# potenciostat.net
KiCad netlist of a schematic drawn in EAGLE
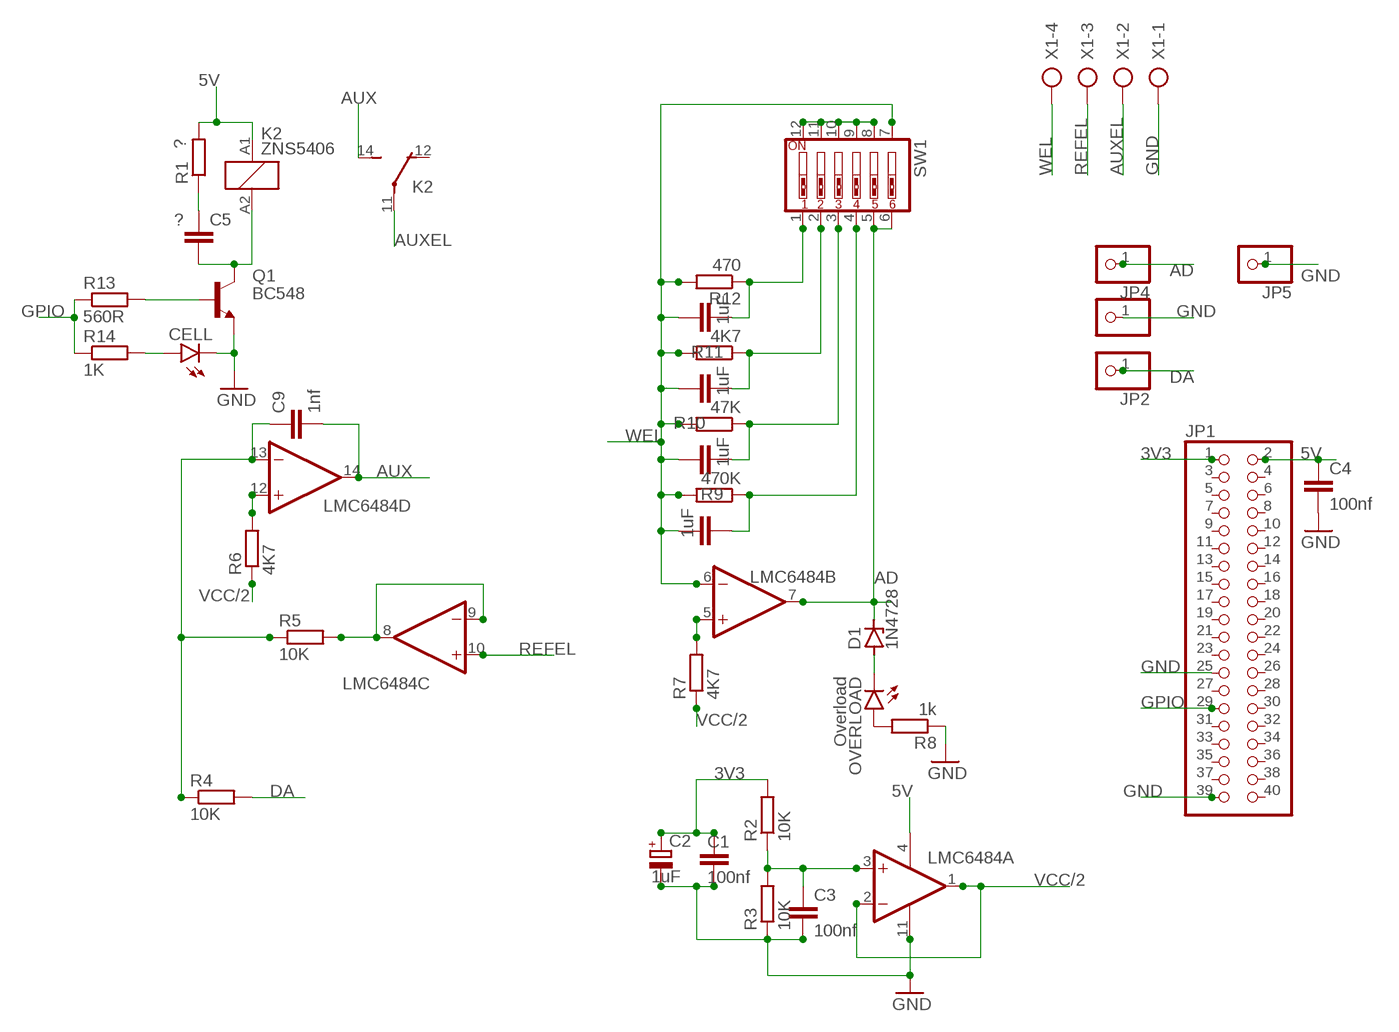
[diagram p0: schematic, sheet 1]

(export (version "E")
  (design (tool "Eeschema 10.0.6"))
  (components
    (comp (ref "C1")
      (value "100nf")
      (footprint "eagle-import:C050-035X075")
      (libsource (lib "eagle-import") (part "C-EU050-035X075"))
    )
    (comp (ref "C2")
      (value "1uF")
      (footprint "eagle-import:E2,5-5")
      (libsource (lib "eagle-import") (part "CPOL-EUE2.5-5"))
    )
    (comp (ref "C3")
      (value "100nf")
      (footprint "eagle-import:C050-035X075")
      (libsource (lib "eagle-import") (part "C-EU050-035X075"))
    )
    (comp (ref "C4")
      (value "100nf")
      (footprint "eagle-import:C050-035X075")
      (libsource (lib "eagle-import") (part "C-EU050-035X075"))
    )
    (comp (ref "C5")
      (value "?")
      (footprint "eagle-import:C050-035X075")
      (libsource (lib "eagle-import") (part "C-EU050-035X075"))
    )
    (comp (ref "C6")
      (value "1uF")
      (footprint "eagle-import:C050-035X075")
      (libsource (lib "eagle-import") (part "C-EU050-035X075"))
    )
    (comp (ref "C7")
      (value "1uF")
      (footprint "eagle-import:C050-035X075")
      (libsource (lib "eagle-import") (part "C-EU050-035X075"))
    )
    (comp (ref "C8")
      (value "1uF")
      (footprint "eagle-import:C050-035X075")
      (libsource (lib "eagle-import") (part "C-EU050-035X075"))
    )
    (comp (ref "C9")
      (value "1nf")
      (footprint "eagle-import:C050-035X075")
      (libsource (lib "eagle-import") (part "C-EU050-035X075"))
    )
    (comp (ref "C10")
      (value "1uF")
      (footprint "eagle-import:C050-035X075")
      (libsource (lib "eagle-import") (part "C-EU050-035X075"))
    )
    (comp (ref "CELL")
      (value "TLLG4400")
      (footprint "eagle-import:LED3MM")
      (fields (field (name "MF") "VISHAY SEMICONDUCTOR"))
      (libsource (lib "eagle-import") (part "TLLG4400"))
    )
    (comp (ref "D1")
      (value "1N4728")
      (footprint "eagle-import:DO41Z10")
      (libsource (lib "eagle-import") (part "1N4728"))
    )
    (comp (ref "JP1")
      (value "PINHD-2X20/90")
      (footprint "eagle-import:2X20_90")
      (libsource (lib "eagle-import") (part "PINHD-2X20/90"))
    )
    (comp (ref "JP2")
      (value "PINHD-1X1")
      (footprint "eagle-import:1X01")
      (libsource (lib "eagle-import") (part "PINHD-1X1"))
    )
    (comp (ref "JP3")
      (value "PINHD-1X1")
      (footprint "eagle-import:1X01")
      (libsource (lib "eagle-import") (part "PINHD-1X1"))
    )
    (comp (ref "JP4")
      (value "PINHD-1X1")
      (footprint "eagle-import:1X01")
      (libsource (lib "eagle-import") (part "PINHD-1X1"))
    )
    (comp (ref "JP5")
      (value "PINHD-1X1")
      (footprint "eagle-import:1X01")
      (libsource (lib "eagle-import") (part "PINHD-1X1"))
    )
    (comp (ref "K2")
      (value "ZNS5406")
      (footprint "eagle-import:ZN5")
      (libsource (lib "eagle-import") (part "ZNS5406"))
    )
    (comp (ref "LMC6484")
      (value "TL074P")
      (footprint "eagle-import:DIL14")
      (libsource (lib "eagle-import") (part "TL074P"))
    )
    (comp (ref "OVERLOAD")
      (value "Overload")
      (footprint "eagle-import:LED3MM")
      (fields (field (name "MF") "VISHAY SEMICONDUCTOR"))
      (libsource (lib "eagle-import") (part "TLLG4400"))
    )
    (comp (ref "Q1")
      (value "BC548")
      (footprint "eagle-import:TO92-EBC")
      (libsource (lib "eagle-import") (part "BC548"))
    )
    (comp (ref "R1")
      (value "?")
      (footprint "eagle-import:0207_7")
      (libsource (lib "eagle-import") (part "R-EU_0207/7"))
    )
    (comp (ref "R2")
      (value "10K")
      (footprint "eagle-import:0207_7")
      (libsource (lib "eagle-import") (part "R-EU_0207/7"))
    )
    (comp (ref "R3")
      (value "10K")
      (footprint "eagle-import:0207_7")
      (libsource (lib "eagle-import") (part "R-EU_0207/7"))
    )
    (comp (ref "R4")
      (value "10K")
      (footprint "eagle-import:0207_7")
      (libsource (lib "eagle-import") (part "R-EU_0207/7"))
    )
    (comp (ref "R5")
      (value "10K")
      (footprint "eagle-import:0207_7")
      (libsource (lib "eagle-import") (part "R-EU_0207/7"))
    )
    (comp (ref "R6")
      (value "4K7")
      (footprint "eagle-import:0207_7")
      (libsource (lib "eagle-import") (part "R-EU_0207/7"))
    )
    (comp (ref "R7")
      (value "4K7")
      (footprint "eagle-import:0207_7")
      (libsource (lib "eagle-import") (part "R-EU_0207/7"))
    )
    (comp (ref "R8")
      (value "1k")
      (footprint "eagle-import:0207_7")
      (libsource (lib "eagle-import") (part "R-EU_0207/7"))
    )
    (comp (ref "R9")
      (value "470K")
      (footprint "eagle-import:0207_7")
      (libsource (lib "eagle-import") (part "R-EU_0207/7"))
    )
    (comp (ref "R10")
      (value "47K")
      (footprint "eagle-import:0207_7")
      (libsource (lib "eagle-import") (part "R-EU_0207/7"))
    )
    (comp (ref "R11")
      (value "4K7")
      (footprint "eagle-import:0207_7")
      (libsource (lib "eagle-import") (part "R-EU_0207/7"))
    )
    (comp (ref "R12")
      (value "470")
      (footprint "eagle-import:0207_7")
      (libsource (lib "eagle-import") (part "R-EU_0207/7"))
    )
    (comp (ref "R13")
      (value "560R")
      (footprint "eagle-import:0207_7")
      (libsource (lib "eagle-import") (part "R-EU_0207/7"))
    )
    (comp (ref "R14")
      (value "1K")
      (footprint "eagle-import:0207_7")
      (libsource (lib "eagle-import") (part "R-EU_0207/7"))
    )
    (comp (ref "SW1")
      (value "SW_DIP-6")
      (footprint "eagle-import:EDG-06")
      (libsource (lib "eagle-import") (part "SW_DIP-6"))
    )
    (comp (ref "X1")
      (value "AK500/4")
      (footprint "eagle-import:AK500_4")
      (libsource (lib "eagle-import") (part "AK500/4"))
    )
  )
  (nets
    (net (code "1") (name "/3V3") (class "Default")
      (node (ref "C1") (pin "1") (pinfunction "1_1") (pintype "passive"))
      (node (ref "C2") (pin "+") (pinfunction "+_+") (pintype "passive"))
      (node (ref "JP1") (pin "1") (pinfunction "1_1") (pintype "passive"))
      (node (ref "R2") (pin "2") (pinfunction "2_2") (pintype "passive"))
    )
    (net (code "2") (name "/5V") (class "Default")
      (node (ref "C4") (pin "1") (pinfunction "1_1") (pintype "passive"))
      (node (ref "JP1") (pin "2") (pinfunction "2_2") (pintype "passive"))
      (node (ref "K2") (pin "A1") (pinfunction "1_A1") (pintype "passive"))
      (node (ref "LMC6484") (pin "4") (pinfunction "V+_4") (pintype "power_in"))
      (node (ref "R1") (pin "2") (pinfunction "2_2") (pintype "passive"))
    )
    (net (code "3") (name "/AD") (class "Default")
      (node (ref "D1") (pin "C") (pinfunction "C_C") (pintype "passive"))
      (node (ref "JP4") (pin "1") (pinfunction "1_1") (pintype "passive"))
      (node (ref "LMC6484") (pin "7") (pinfunction "OUT_7") (pintype "output"))
      (node (ref "SW1") (pin "5") (pinfunction "5_5") (pintype "passive"))
      (node (ref "SW1") (pin "6") (pinfunction "6_6") (pintype "passive"))
    )
    (net (code "4") (name "/AUX") (class "Default")
      (node (ref "C9") (pin "2") (pinfunction "2_2") (pintype "passive"))
      (node (ref "K2") (pin "14") (pinfunction "S_14") (pintype "passive"))
      (node (ref "LMC6484") (pin "14") (pinfunction "OUT_14") (pintype "output"))
    )
    (net (code "5") (name "/AUXEL") (class "Default")
      (node (ref "K2") (pin "11") (pinfunction "P_11") (pintype "passive"))
      (node (ref "X1") (pin "2") (pinfunction "KL_2") (pintype "passive"))
    )
    (net (code "6") (name "/DA") (class "Default")
      (node (ref "JP2") (pin "1") (pinfunction "1_1") (pintype "passive"))
      (node (ref "R4") (pin "2") (pinfunction "2_2") (pintype "passive"))
    )
    (net (code "7") (name "/GPIO") (class "Default")
      (node (ref "JP1") (pin "29") (pinfunction "29_29") (pintype "passive"))
      (node (ref "R13") (pin "1") (pinfunction "1_1") (pintype "passive"))
      (node (ref "R14") (pin "1") (pinfunction "1_1") (pintype "passive"))
    )
    (net (code "8") (name "/REFEL") (class "Default")
      (node (ref "LMC6484") (pin "10") (pinfunction "+IN_10") (pintype "input"))
      (node (ref "X1") (pin "3") (pinfunction "KL_3") (pintype "passive"))
    )
    (net (code "9") (name "/VCC{slash}2") (class "Default")
      (node (ref "LMC6484") (pin "1") (pinfunction "OUT_1") (pintype "output"))
      (node (ref "LMC6484") (pin "2") (pinfunction "-IN_2") (pintype "input"))
      (node (ref "R6") (pin "1") (pinfunction "1_1") (pintype "passive"))
      (node (ref "R7") (pin "1") (pinfunction "1_1") (pintype "passive"))
    )
    (net (code "10") (name "/WEL") (class "Default")
      (node (ref "C10") (pin "1") (pinfunction "1_1") (pintype "passive"))
      (node (ref "C6") (pin "1") (pinfunction "1_1") (pintype "passive"))
      (node (ref "C7") (pin "1") (pinfunction "1_1") (pintype "passive"))
      (node (ref "C8") (pin "1") (pinfunction "1_1") (pintype "passive"))
      (node (ref "LMC6484") (pin "6") (pinfunction "-IN_6") (pintype "input"))
      (node (ref "R10") (pin "2") (pinfunction "2_2") (pintype "passive"))
      (node (ref "R11") (pin "2") (pinfunction "2_2") (pintype "passive"))
      (node (ref "R12") (pin "2") (pinfunction "2_2") (pintype "passive"))
      (node (ref "R9") (pin "2") (pinfunction "2_2") (pintype "passive"))
      (node (ref "SW1") (pin "7") (pinfunction "7_7") (pintype "passive"))
      (node (ref "X1") (pin "4") (pinfunction "KL_4") (pintype "passive"))
    )
    (net (code "11") (name "GND") (class "Default")
      (node (ref "C1") (pin "2") (pinfunction "2_2") (pintype "passive"))
      (node (ref "C2") (pin "-") (pinfunction "-_-") (pintype "passive"))
      (node (ref "C3") (pin "2") (pinfunction "2_2") (pintype "passive"))
      (node (ref "C4") (pin "2") (pinfunction "2_2") (pintype "passive"))
      (node (ref "CELL") (pin "K") (pinfunction "C_K") (pintype "passive"))
      (node (ref "JP1") (pin "25") (pinfunction "25_25") (pintype "passive"))
      (node (ref "JP1") (pin "39") (pinfunction "39_39") (pintype "passive"))
      (node (ref "JP3") (pin "1") (pinfunction "1_1") (pintype "passive"))
      (node (ref "JP5") (pin "1") (pinfunction "1_1") (pintype "passive"))
      (node (ref "LMC6484") (pin "11") (pinfunction "V-_11") (pintype "power_in"))
      (node (ref "Q1") (pin "E") (pinfunction "E_E") (pintype "passive"))
      (node (ref "R3") (pin "1") (pinfunction "1_1") (pintype "passive"))
      (node (ref "R8") (pin "1") (pinfunction "1_1") (pintype "passive"))
      (node (ref "X1") (pin "1") (pinfunction "KL_1") (pintype "passive"))
    )
    (net (code "12") (name "Net-(C5-Pad1)") (class "Default")
      (node (ref "C5") (pin "1") (pinfunction "1_1") (pintype "passive"))
      (node (ref "R1") (pin "1") (pinfunction "1_1") (pintype "passive"))
    )
    (net (code "13") (name "Net-(C6-Pad2)") (class "Default")
      (node (ref "C6") (pin "2") (pinfunction "2_2") (pintype "passive"))
      (node (ref "R9") (pin "1") (pinfunction "1_1") (pintype "passive"))
      (node (ref "SW1") (pin "4") (pinfunction "4_4") (pintype "passive"))
    )
    (net (code "14") (name "Net-(C7-Pad2)") (class "Default")
      (node (ref "C7") (pin "2") (pinfunction "2_2") (pintype "passive"))
      (node (ref "R12") (pin "1") (pinfunction "1_1") (pintype "passive"))
      (node (ref "SW1") (pin "1") (pinfunction "1_1") (pintype "passive"))
    )
    (net (code "15") (name "Net-(C8-Pad2)") (class "Default")
      (node (ref "C8") (pin "2") (pinfunction "2_2") (pintype "passive"))
      (node (ref "R11") (pin "1") (pinfunction "1_1") (pintype "passive"))
      (node (ref "SW1") (pin "2") (pinfunction "2_2") (pintype "passive"))
    )
    (net (code "16") (name "Net-(C10-Pad2)") (class "Default")
      (node (ref "C10") (pin "2") (pinfunction "2_2") (pintype "passive"))
      (node (ref "R10") (pin "1") (pinfunction "1_1") (pintype "passive"))
      (node (ref "SW1") (pin "3") (pinfunction "3_3") (pintype "passive"))
    )
    (net (code "17") (name "Net-(CELL-PadA)") (class "Default")
      (node (ref "CELL") (pin "A") (pinfunction "A_A") (pintype "passive"))
      (node (ref "R14") (pin "2") (pinfunction "2_2") (pintype "passive"))
    )
    (net (code "18") (name "Net-(K2A-2)") (class "Default")
      (node (ref "C5") (pin "2") (pinfunction "2_2") (pintype "passive"))
      (node (ref "K2") (pin "A2") (pinfunction "2_A2") (pintype "passive"))
      (node (ref "Q1") (pin "C") (pinfunction "C_C") (pintype "passive"))
    )
    (net (code "19") (name "Net-(LMC6484A-+IN)") (class "Default")
      (node (ref "C3") (pin "1") (pinfunction "1_1") (pintype "passive"))
      (node (ref "LMC6484") (pin "3") (pinfunction "+IN_3") (pintype "input"))
      (node (ref "R2") (pin "1") (pinfunction "1_1") (pintype "passive"))
      (node (ref "R3") (pin "2") (pinfunction "2_2") (pintype "passive"))
    )
    (net (code "20") (name "Net-(LMC6484B-+IN)") (class "Default")
      (node (ref "LMC6484") (pin "5") (pinfunction "+IN_5") (pintype "input"))
      (node (ref "R7") (pin "2") (pinfunction "2_2") (pintype "passive"))
    )
    (net (code "21") (name "Net-(LMC6484C--IN)") (class "Default")
      (node (ref "LMC6484") (pin "8") (pinfunction "OUT_8") (pintype "output"))
      (node (ref "LMC6484") (pin "9") (pinfunction "-IN_9") (pintype "input"))
      (node (ref "R5") (pin "2") (pinfunction "2_2") (pintype "passive"))
    )
    (net (code "22") (name "Net-(LMC6484D-+IN)") (class "Default")
      (node (ref "LMC6484") (pin "12") (pinfunction "+IN_12") (pintype "input"))
      (node (ref "R6") (pin "2") (pinfunction "2_2") (pintype "passive"))
    )
    (net (code "23") (name "Net-(LMC6484D--IN)") (class "Default")
      (node (ref "C9") (pin "1") (pinfunction "1_1") (pintype "passive"))
      (node (ref "LMC6484") (pin "13") (pinfunction "-IN_13") (pintype "input"))
      (node (ref "R4") (pin "1") (pinfunction "1_1") (pintype "passive"))
      (node (ref "R5") (pin "1") (pinfunction "1_1") (pintype "passive"))
    )
    (net (code "24") (name "Net-(OVERLOAD-C)") (class "Default")
      (node (ref "D1") (pin "A") (pinfunction "A_A") (pintype "passive"))
      (node (ref "OVERLOAD") (pin "K") (pinfunction "C_K") (pintype "passive"))
    )
    (net (code "25") (name "Net-(OVERLOAD-PadA)") (class "Default")
      (node (ref "OVERLOAD") (pin "A") (pinfunction "A_A") (pintype "passive"))
      (node (ref "R8") (pin "2") (pinfunction "2_2") (pintype "passive"))
    )
    (net (code "26") (name "Net-(Q1-PadB)") (class "Default")
      (node (ref "Q1") (pin "B") (pinfunction "B_B") (pintype "passive"))
      (node (ref "R13") (pin "2") (pinfunction "2_2") (pintype "passive"))
    )
    (net (code "27") (name "Net-(SW1-Pad10)") (class "Default")
      (node (ref "SW1") (pin "10") (pinfunction "10_10") (pintype "passive"))
      (node (ref "SW1") (pin "11") (pinfunction "11_11") (pintype "passive"))
      (node (ref "SW1") (pin "12") (pinfunction "12_12") (pintype "passive"))
      (node (ref "SW1") (pin "8") (pinfunction "8_8") (pintype "passive"))
      (node (ref "SW1") (pin "9") (pinfunction "9_9") (pintype "passive"))
    )
    (net (code "28") (name "unconnected-(JP1-Pad3)") (class "Default")
      (node (ref "JP1") (pin "3") (pinfunction "3_3") (pintype "passive"))
    )
    (net (code "29") (name "unconnected-(JP1-Pad4)") (class "Default")
      (node (ref "JP1") (pin "4") (pinfunction "4_4") (pintype "passive"))
    )
    (net (code "30") (name "unconnected-(JP1-Pad5)") (class "Default")
      (node (ref "JP1") (pin "5") (pinfunction "5_5") (pintype "passive"))
    )
    (net (code "31") (name "unconnected-(JP1-Pad6)") (class "Default")
      (node (ref "JP1") (pin "6") (pinfunction "6_6") (pintype "passive"))
    )
    (net (code "32") (name "unconnected-(JP1-Pad7)") (class "Default")
      (node (ref "JP1") (pin "7") (pinfunction "7_7") (pintype "passive"))
    )
    (net (code "33") (name "unconnected-(JP1-Pad8)") (class "Default")
      (node (ref "JP1") (pin "8") (pinfunction "8_8") (pintype "passive"))
    )
    (net (code "34") (name "unconnected-(JP1-Pad9)") (class "Default")
      (node (ref "JP1") (pin "9") (pinfunction "9_9") (pintype "passive"))
    )
    (net (code "35") (name "unconnected-(JP1-Pad10)") (class "Default")
      (node (ref "JP1") (pin "10") (pinfunction "10_10") (pintype "passive"))
    )
    (net (code "36") (name "unconnected-(JP1-Pad11)") (class "Default")
      (node (ref "JP1") (pin "11") (pinfunction "11_11") (pintype "passive"))
    )
    (net (code "37") (name "unconnected-(JP1-Pad12)") (class "Default")
      (node (ref "JP1") (pin "12") (pinfunction "12_12") (pintype "passive"))
    )
    (net (code "38") (name "unconnected-(JP1-Pad13)") (class "Default")
      (node (ref "JP1") (pin "13") (pinfunction "13_13") (pintype "passive"))
    )
    (net (code "39") (name "unconnected-(JP1-Pad14)") (class "Default")
      (node (ref "JP1") (pin "14") (pinfunction "14_14") (pintype "passive"))
    )
    (net (code "40") (name "unconnected-(JP1-Pad15)") (class "Default")
      (node (ref "JP1") (pin "15") (pinfunction "15_15") (pintype "passive"))
    )
    (net (code "41") (name "unconnected-(JP1-Pad16)") (class "Default")
      (node (ref "JP1") (pin "16") (pinfunction "16_16") (pintype "passive"))
    )
    (net (code "42") (name "unconnected-(JP1-Pad17)") (class "Default")
      (node (ref "JP1") (pin "17") (pinfunction "17_17") (pintype "passive"))
    )
    (net (code "43") (name "unconnected-(JP1-Pad18)") (class "Default")
      (node (ref "JP1") (pin "18") (pinfunction "18_18") (pintype "passive"))
    )
    (net (code "44") (name "unconnected-(JP1-Pad19)") (class "Default")
      (node (ref "JP1") (pin "19") (pinfunction "19_19") (pintype "passive"))
    )
    (net (code "45") (name "unconnected-(JP1-Pad20)") (class "Default")
      (node (ref "JP1") (pin "20") (pinfunction "20_20") (pintype "passive"))
    )
    (net (code "46") (name "unconnected-(JP1-Pad21)") (class "Default")
      (node (ref "JP1") (pin "21") (pinfunction "21_21") (pintype "passive"))
    )
    (net (code "47") (name "unconnected-(JP1-Pad22)") (class "Default")
      (node (ref "JP1") (pin "22") (pinfunction "22_22") (pintype "passive"))
    )
    (net (code "48") (name "unconnected-(JP1-Pad23)") (class "Default")
      (node (ref "JP1") (pin "23") (pinfunction "23_23") (pintype "passive"))
    )
    (net (code "49") (name "unconnected-(JP1-Pad24)") (class "Default")
      (node (ref "JP1") (pin "24") (pinfunction "24_24") (pintype "passive"))
    )
    (net (code "50") (name "unconnected-(JP1-Pad26)") (class "Default")
      (node (ref "JP1") (pin "26") (pinfunction "26_26") (pintype "passive"))
    )
    (net (code "51") (name "unconnected-(JP1-Pad27)") (class "Default")
      (node (ref "JP1") (pin "27") (pinfunction "27_27") (pintype "passive"))
    )
    (net (code "52") (name "unconnected-(JP1-Pad28)") (class "Default")
      (node (ref "JP1") (pin "28") (pinfunction "28_28") (pintype "passive"))
    )
    (net (code "53") (name "unconnected-(JP1-Pad30)") (class "Default")
      (node (ref "JP1") (pin "30") (pinfunction "30_30") (pintype "passive"))
    )
    (net (code "54") (name "unconnected-(JP1-Pad31)") (class "Default")
      (node (ref "JP1") (pin "31") (pinfunction "31_31") (pintype "passive"))
    )
    (net (code "55") (name "unconnected-(JP1-Pad32)") (class "Default")
      (node (ref "JP1") (pin "32") (pinfunction "32_32") (pintype "passive"))
    )
    (net (code "56") (name "unconnected-(JP1-Pad33)") (class "Default")
      (node (ref "JP1") (pin "33") (pinfunction "33_33") (pintype "passive"))
    )
    (net (code "57") (name "unconnected-(JP1-Pad34)") (class "Default")
      (node (ref "JP1") (pin "34") (pinfunction "34_34") (pintype "passive"))
    )
    (net (code "58") (name "unconnected-(JP1-Pad35)") (class "Default")
      (node (ref "JP1") (pin "35") (pinfunction "35_35") (pintype "passive"))
    )
    (net (code "59") (name "unconnected-(JP1-Pad36)") (class "Default")
      (node (ref "JP1") (pin "36") (pinfunction "36_36") (pintype "passive"))
    )
    (net (code "60") (name "unconnected-(JP1-Pad37)") (class "Default")
      (node (ref "JP1") (pin "37") (pinfunction "37_37") (pintype "passive"))
    )
    (net (code "61") (name "unconnected-(JP1-Pad38)") (class "Default")
      (node (ref "JP1") (pin "38") (pinfunction "38_38") (pintype "passive"))
    )
    (net (code "62") (name "unconnected-(JP1-Pad40)") (class "Default")
      (node (ref "JP1") (pin "40") (pinfunction "40_40") (pintype "passive"))
    )
    (net (code "63") (name "unconnected-(K2B-O-Pad12)") (class "Default")
      (node (ref "K2") (pin "12") (pinfunction "O_12") (pintype "passive"))
    )
  )
)
